# FMU_IO_ports.net
KiCad netlist of a schematic drawn in Altium Designer
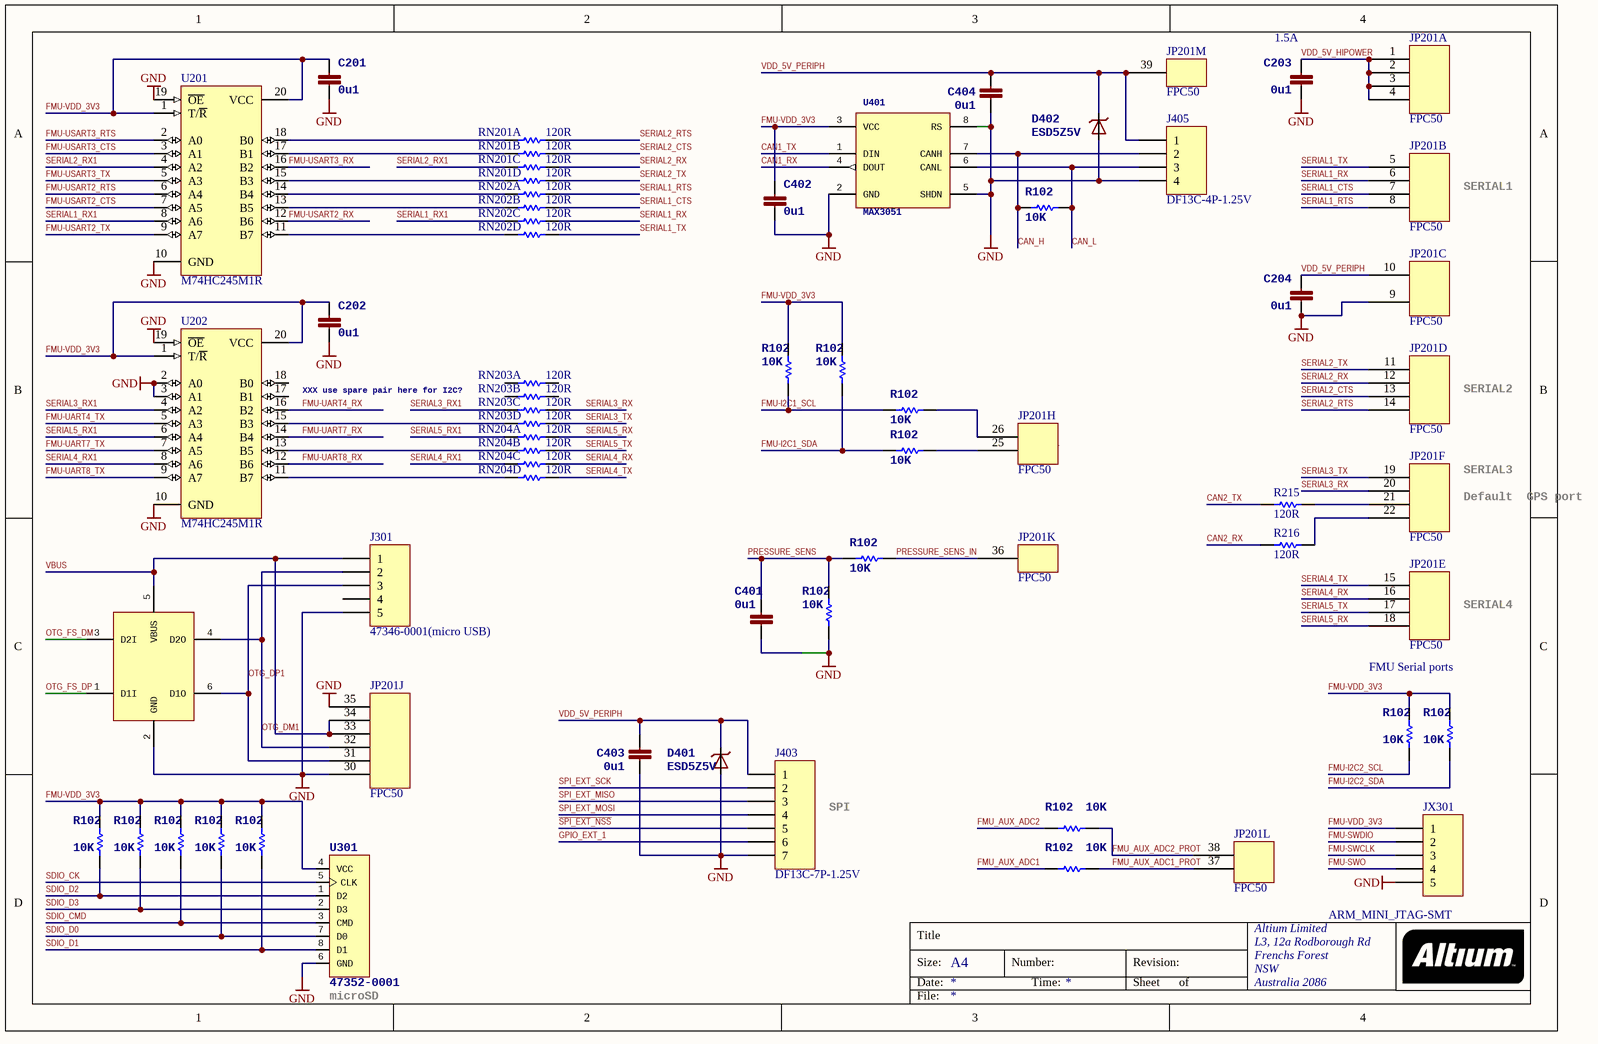
[diagram p0: FMU IO ports.SchDoc]

(export (version "E")
  (design (tool "Eeschema 10.0.6"))
  (components
    (comp (ref "C201")
      (value "0u1")
      (footprint "0603-CAP")
      (description "<b>Capacitor</b>\nStandard 0603 ceramic capacitor, and 0.1\" leaded capacitor.")
      (fields
        (field (name "PARTNO") "CC0402ZRY5V7BB104")
        (field (name ">NAME") "C201")
        (field (name ">VALUE") "0u1")
      )
      (libsource (lib "pixhawk2") (part "CAP0402"))
    )
    (comp (ref "C202")
      (value "0u1")
      (footprint "0603-CAP")
      (description "<b>Capacitor</b>\nStandard 0603 ceramic capacitor, and 0.1\" leaded capacitor.")
      (fields
        (field (name "PARTNO") "CC0402ZRY5V7BB104")
        (field (name ">NAME") "C202")
        (field (name ">VALUE") "0u1")
      )
      (libsource (lib "pixhawk2") (part "CAP0402"))
    )
    (comp (ref "C203")
      (value "0u1")
      (footprint "0603-CAP")
      (description "<b>Capacitor</b>\nStandard 0603 ceramic capacitor, and 0.1\" leaded capacitor.")
      (fields
        (field (name "PARTNO") "CC0805ZKY5V6BB106")
        (field (name ">NAME") "C203")
        (field (name ">VALUE") "0u1")
      )
      (libsource (lib "pixhawk2") (part "CAP0805"))
    )
    (comp (ref "C204")
      (value "0u1")
      (footprint "0603-CAP")
      (description "<b>Capacitor</b>\nStandard 0603 ceramic capacitor, and 0.1\" leaded capacitor.")
      (fields
        (field (name "PARTNO") "CC0805ZKY5V6BB106")
        (field (name ">NAME") "C204")
        (field (name ">VALUE") "0u1")
      )
      (libsource (lib "pixhawk2") (part "CAP0805"))
    )
    (comp (ref "C401")
      (value "0u1")
      (footprint "0603-CAP")
      (description "<b>Capacitor</b>\nStandard 0603 ceramic capacitor, and 0.1\" leaded capacitor.")
      (fields
        (field (name "PARTNO") "CC0402ZRY5V7BB104")
        (field (name ">NAME") "C401")
        (field (name ">VALUE") "0u1")
      )
      (libsource (lib "pixhawk2") (part "CAP0402"))
    )
    (comp (ref "C402")
      (value "0u1")
      (footprint "0603-CAP")
      (description "<b>Capacitor</b>\nStandard 0603 ceramic capacitor, and 0.1\" leaded capacitor.")
      (fields
        (field (name "PARTNO") "CC0402ZRY5V7BB104")
        (field (name ">NAME") "C402")
        (field (name ">VALUE") "0u1")
      )
      (libsource (lib "pixhawk2") (part "CAP0402"))
    )
    (comp (ref "C403")
      (value "0u1")
      (footprint "0603-CAP")
      (description "<b>Capacitor</b>\nStandard 0603 ceramic capacitor, and 0.1\" leaded capacitor.")
      (fields
        (field (name "PARTNO") "CC0805ZKY5V6BB106")
        (field (name ">NAME") "C403")
        (field (name ">VALUE") "0u1")
      )
      (libsource (lib "pixhawk2") (part "CAP0805"))
    )
    (comp (ref "C404")
      (value "0u1")
      (footprint "0603-CAP")
      (description "<b>Capacitor</b>\nStandard 0603 ceramic capacitor, and 0.1\" leaded capacitor.")
      (fields
        (field (name "PARTNO") "CC0805ZKY5V6BB106")
        (field (name ">NAME") "C404")
        (field (name ">VALUE") "0u1")
      )
      (libsource (lib "pixhawk2") (part "CAP0805"))
    )
    (comp (ref "D401") (value "ESD5Z5V") (footprint "SOD523") (libsource (lib "pixhawk2") (part "DIODE-TVS")))
    (comp (ref "D402") (value "ESD5Z5V") (footprint "SOD523") (libsource (lib "pixhawk2") (part "DIODE-TVS")))
    (comp (ref "J301")
      (value "47346-0001(micro USB)")
      (footprint "HDR1X5")
      (description "Header, 5-Pin")
      (fields (field (name "PUBLISHER") "Altium Limited"))
      (libsource (lib "Miscellaneous Connectors") (part "Header 5"))
    )
    (comp (ref "J403")
      (value "DF13C-7P-1.25V")
      (footprint "HDR1X7")
      (description "Header, 7-Pin")
      (fields (field (name "PUBLISHER") "Altium Limited"))
      (libsource (lib "Miscellaneous Connectors") (part "Header 7"))
    )
    (comp (ref "J405")
      (value "DF13C-4P-1.25V")
      (footprint "HDR1X4")
      (description "Header, 4-Pin")
      (fields (field (name "PUBLISHER") "Altium Limited"))
      (libsource (lib "Miscellaneous Connectors") (part "Header 4"))
    )
    (comp (ref "JP201") (value "FPC50") (footprint "FPC-0.5-50下接带锁") (libsource (lib "") (part "FPC50_1")))
    (comp (ref "JX301")
      (value "ARM_MINI_JTAG-SMT")
      (footprint "HDR1X5")
      (description "Header, 5-Pin")
      (fields (field (name "PUBLISHER") "Altium Limited"))
      (libsource (lib "Miscellaneous Connectors") (part "Header 5"))
    )
    (comp (ref "R215")
      (value "120R")
      (footprint "AXIAL-0.5")
      (description "Semiconductor Resistor")
      (fields (field (name "Comment") "Res Semi") (field (name "PUBLISHER") "Altium Limited"))
      (libsource (lib "Miscellaneous Devices") (part "Res Semi"))
    )
    (comp (ref "R216")
      (value "120R")
      (footprint "AXIAL-0.5")
      (description "Semiconductor Resistor")
      (fields (field (name "Comment") "Res Semi") (field (name "PUBLISHER") "Altium Limited"))
      (libsource (lib "Miscellaneous Devices") (part "Res Semi"))
    )
    (comp (ref "R301")
      (value "10K")
      (footprint "0603-RES")
      (fields
        (field (name "PARTNO") "RC0402FR-0710KL")
        (field (name ">NAME") "R102")
        (field (name ">VALUE") "10K")
      )
      (libsource (lib "PX4") (part "RESISTOR0402-RES"))
    )
    (comp (ref "R302")
      (value "10K")
      (footprint "0603-RES")
      (fields
        (field (name "PARTNO") "RC0402FR-0710KL")
        (field (name ">NAME") "R102")
        (field (name ">VALUE") "10K")
      )
      (libsource (lib "PX4") (part "RESISTOR0402-RES"))
    )
    (comp (ref "R303")
      (value "10K")
      (footprint "0603-RES")
      (fields
        (field (name "PARTNO") "RC0402FR-0710KL")
        (field (name ">NAME") "R102")
        (field (name ">VALUE") "10K")
      )
      (libsource (lib "PX4") (part "RESISTOR0402-RES"))
    )
    (comp (ref "R304")
      (value "10K")
      (footprint "0603-RES")
      (fields
        (field (name "PARTNO") "RC0402FR-0710KL")
        (field (name ">NAME") "R102")
        (field (name ">VALUE") "10K")
      )
      (libsource (lib "PX4") (part "RESISTOR0402-RES"))
    )
    (comp (ref "R305")
      (value "10K")
      (footprint "0603-RES")
      (fields
        (field (name "PARTNO") "RC0402FR-0710KL")
        (field (name ">NAME") "R102")
        (field (name ">VALUE") "10K")
      )
      (libsource (lib "PX4") (part "RESISTOR0402-RES"))
    )
    (comp (ref "R306")
      (value "10K")
      (footprint "0603-RES")
      (fields
        (field (name "PARTNO") "RC0402FR-0710KL")
        (field (name ">NAME") "R102")
        (field (name ">VALUE") "10K")
      )
      (libsource (lib "PX4") (part "RESISTOR0402-RES"))
    )
    (comp (ref "R307")
      (value "10K")
      (footprint "0603-RES")
      (fields
        (field (name "PARTNO") "RC0402FR-0710KL")
        (field (name ">NAME") "R102")
        (field (name ">VALUE") "10K")
      )
      (libsource (lib "PX4") (part "RESISTOR0402-RES"))
    )
    (comp (ref "R401")
      (value "10K")
      (footprint "0603-RES")
      (fields
        (field (name "PARTNO") "RC0402FR-0710KL")
        (field (name ">NAME") "R102")
        (field (name ">VALUE") "10K")
      )
      (libsource (lib "PX4") (part "RESISTOR0402-RES"))
    )
    (comp (ref "R402")
      (value "10K")
      (footprint "0603-RES")
      (fields
        (field (name "PARTNO") "RC0402FR-0710KL")
        (field (name ">NAME") "R102")
        (field (name ">VALUE") "10K")
      )
      (libsource (lib "PX4") (part "RESISTOR0402-RES"))
    )
    (comp (ref "R403")
      (value "10K")
      (footprint "0603-RES")
      (fields
        (field (name "PARTNO") "RC0402FR-0710KL")
        (field (name ">NAME") "R102")
        (field (name ">VALUE") "10K")
      )
      (libsource (lib "PX4") (part "RESISTOR0402-RES"))
    )
    (comp (ref "R404")
      (value "10K")
      (footprint "0603-RES")
      (fields
        (field (name "PARTNO") "RC0402FR-0710KL")
        (field (name ">NAME") "R102")
        (field (name ">VALUE") "10K")
      )
      (libsource (lib "PX4") (part "RESISTOR0402-RES"))
    )
    (comp (ref "R405")
      (value "10K")
      (footprint "0603-RES")
      (fields
        (field (name "PARTNO") "RC0402FR-0710KL")
        (field (name ">NAME") "R102")
        (field (name ">VALUE") "10K")
      )
      (libsource (lib "PX4") (part "RESISTOR0402-RES"))
    )
    (comp (ref "R406")
      (value "10K")
      (footprint "0603-RES")
      (fields
        (field (name "PARTNO") "RC0402FR-0710KL")
        (field (name ">NAME") "R102")
        (field (name ">VALUE") "10K")
      )
      (libsource (lib "PX4") (part "RESISTOR0402-RES"))
    )
    (comp (ref "R407")
      (value "10K")
      (footprint "0603-RES")
      (fields
        (field (name "PARTNO") "RC0402FR-0710KL")
        (field (name ">NAME") "R102")
        (field (name ">VALUE") "10K")
      )
      (libsource (lib "PX4") (part "RESISTOR0402-RES"))
    )
    (comp (ref "R408")
      (value "10K")
      (footprint "0603-RES")
      (fields
        (field (name "PARTNO") "RC0402FR-0710KL")
        (field (name ">NAME") "R102")
        (field (name ">VALUE") "10K")
      )
      (libsource (lib "PX4") (part "RESISTOR0402-RES"))
    )
    (comp (ref "R409")
      (value "10K")
      (footprint "0603-RES")
      (fields
        (field (name "PARTNO") "RC0402FR-0710KL")
        (field (name ">NAME") "R102")
        (field (name ">VALUE") "10K")
      )
      (libsource (lib "PX4") (part "RESISTOR0402-RES"))
    )
    (comp (ref "RN201A")
      (value "120R")
      (footprint "AXIAL-0.5")
      (description "Semiconductor Resistor")
      (fields (field (name "Comment") "Res Semi") (field (name "PUBLISHER") "Altium Limited"))
      (libsource (lib "Miscellaneous Devices") (part "Res Semi"))
    )
    (comp (ref "RN201B")
      (value "120R")
      (footprint "AXIAL-0.5")
      (description "Semiconductor Resistor")
      (fields (field (name "Comment") "Res Semi") (field (name "PUBLISHER") "Altium Limited"))
      (libsource (lib "Miscellaneous Devices") (part "Res Semi"))
    )
    (comp (ref "RN201C")
      (value "120R")
      (footprint "AXIAL-0.5")
      (description "Semiconductor Resistor")
      (fields (field (name "Comment") "Res Semi") (field (name "PUBLISHER") "Altium Limited"))
      (libsource (lib "Miscellaneous Devices") (part "Res Semi"))
    )
    (comp (ref "RN201D")
      (value "120R")
      (footprint "AXIAL-0.5")
      (description "Semiconductor Resistor")
      (fields (field (name "Comment") "Res Semi") (field (name "PUBLISHER") "Altium Limited"))
      (libsource (lib "Miscellaneous Devices") (part "Res Semi"))
    )
    (comp (ref "RN202A")
      (value "120R")
      (footprint "AXIAL-0.5")
      (description "Semiconductor Resistor")
      (fields (field (name "Comment") "Res Semi") (field (name "PUBLISHER") "Altium Limited"))
      (libsource (lib "Miscellaneous Devices") (part "Res Semi"))
    )
    (comp (ref "RN202B")
      (value "120R")
      (footprint "AXIAL-0.5")
      (description "Semiconductor Resistor")
      (fields (field (name "Comment") "Res Semi") (field (name "PUBLISHER") "Altium Limited"))
      (libsource (lib "Miscellaneous Devices") (part "Res Semi"))
    )
    (comp (ref "RN202C")
      (value "120R")
      (footprint "AXIAL-0.5")
      (description "Semiconductor Resistor")
      (fields (field (name "Comment") "Res Semi") (field (name "PUBLISHER") "Altium Limited"))
      (libsource (lib "Miscellaneous Devices") (part "Res Semi"))
    )
    (comp (ref "RN202D")
      (value "120R")
      (footprint "AXIAL-0.5")
      (description "Semiconductor Resistor")
      (fields (field (name "Comment") "Res Semi") (field (name "PUBLISHER") "Altium Limited"))
      (libsource (lib "Miscellaneous Devices") (part "Res Semi"))
    )
    (comp (ref "RN203A")
      (value "120R")
      (footprint "AXIAL-0.5")
      (description "Semiconductor Resistor")
      (fields (field (name "Comment") "Res Semi") (field (name "PUBLISHER") "Altium Limited"))
      (libsource (lib "Miscellaneous Devices") (part "Res Semi"))
    )
    (comp (ref "RN203B")
      (value "120R")
      (footprint "AXIAL-0.5")
      (description "Semiconductor Resistor")
      (fields (field (name "Comment") "Res Semi") (field (name "PUBLISHER") "Altium Limited"))
      (libsource (lib "Miscellaneous Devices") (part "Res Semi"))
    )
    (comp (ref "RN203C")
      (value "120R")
      (footprint "AXIAL-0.5")
      (description "Semiconductor Resistor")
      (fields (field (name "Comment") "Res Semi") (field (name "PUBLISHER") "Altium Limited"))
      (libsource (lib "Miscellaneous Devices") (part "Res Semi"))
    )
    (comp (ref "RN203D")
      (value "120R")
      (footprint "AXIAL-0.5")
      (description "Semiconductor Resistor")
      (fields (field (name "Comment") "Res Semi") (field (name "PUBLISHER") "Altium Limited"))
      (libsource (lib "Miscellaneous Devices") (part "Res Semi"))
    )
    (comp (ref "RN204A")
      (value "120R")
      (footprint "AXIAL-0.5")
      (description "Semiconductor Resistor")
      (fields (field (name "Comment") "Res Semi") (field (name "PUBLISHER") "Altium Limited"))
      (libsource (lib "Miscellaneous Devices") (part "Res Semi"))
    )
    (comp (ref "RN204B")
      (value "120R")
      (footprint "AXIAL-0.5")
      (description "Semiconductor Resistor")
      (fields (field (name "Comment") "Res Semi") (field (name "PUBLISHER") "Altium Limited"))
      (libsource (lib "Miscellaneous Devices") (part "Res Semi"))
    )
    (comp (ref "RN204C")
      (value "120R")
      (footprint "AXIAL-0.5")
      (description "Semiconductor Resistor")
      (fields (field (name "Comment") "Res Semi") (field (name "PUBLISHER") "Altium Limited"))
      (libsource (lib "Miscellaneous Devices") (part "Res Semi"))
    )
    (comp (ref "RN204D")
      (value "120R")
      (footprint "AXIAL-0.5")
      (description "Semiconductor Resistor")
      (fields (field (name "Comment") "Res Semi") (field (name "PUBLISHER") "Altium Limited"))
      (libsource (lib "Miscellaneous Devices") (part "Res Semi"))
    )
    (comp (ref "U201")
      (value "M74HC245M1R")
      (footprint "TSSOP20")
      (description "Octal Bus Transceiver 3-State Non-Inverting")
      (fields (field (name "PUBLISHER") "Altium Limited"))
      (libsource (lib "ST Interface Line Transceiver") (part "M74HC245M1R"))
    )
    (comp (ref "U202")
      (value "M74HC245M1R")
      (footprint "TSSOP20")
      (description "Octal Bus Transceiver 3-State Non-Inverting")
      (fields (field (name "PUBLISHER") "Altium Limited"))
      (libsource (lib "ST Interface Line Transceiver") (part "M74HC245M1R"))
    )
    (comp (ref "U301")
      (value "2908-05WB-MG")
      (footprint "MICROSD")
      (fields (field (name ">NAME") "U301") (field (name ">VALUE") "47352-0001"))
      (libsource (lib "PX4") (part "MICROSDSDI"))
    )
    (comp (ref "U302")
      (value "NUF2042XV6")
      (footprint "SOT23-6")
      (fields (field (name "PARTNO") "NUF2042XV6T1G"))
      (libsource (lib "PX4") (part "NUF2042XV6"))
    )
    (comp (ref "U401")
      (value "MAX3051")
      (footprint "SOT23-8")
      (description "3.3-V CAN TRANSCEIVER")
      (fields
        (field (name "PARTNO") "MAX3051EKA")
        (field (name ">NAME") "U401")
        (field (name ">VALUE") "MAX3051")
      )
      (libsource (lib "PX4") (part "MAX3051MAX3051EKA"))
    )
  )
  (nets
    (net (code "1") (name "/CAN1_RX") (class "Default")
      (node (ref "U401") (pin "4") (pinfunction "DOUT_4") (pintype "output"))
    )
    (net (code "2") (name "/CAN1_TX") (class "Default")
      (node (ref "U401") (pin "1") (pinfunction "DIN_1") (pintype "passive"))
    )
    (net (code "3") (name "/CAN2_RX") (class "Default")
      (node (ref "R216") (pin "1") (pinfunction "1_1") (pintype "passive"))
    )
    (net (code "4") (name "/CAN2_TX") (class "Default")
      (node (ref "R215") (pin "1") (pinfunction "1_1") (pintype "passive"))
    )
    (net (code "5") (name "/CAN_H") (class "Default")
      (node (ref "J405") (pin "2") (pinfunction "2_2") (pintype "passive"))
      (node (ref "R409") (pin "P$1") (pinfunction "1_P$1") (pintype "passive"))
      (node (ref "U401") (pin "7") (pinfunction "CANH_7") (pintype "passive"))
    )
    (net (code "6") (name "/CAN_L") (class "Default")
      (node (ref "J405") (pin "3") (pinfunction "3_3") (pintype "passive"))
      (node (ref "R409") (pin "P$2") (pinfunction "2_P$2") (pintype "passive"))
      (node (ref "U401") (pin "6") (pinfunction "CANL_6") (pintype "passive"))
    )
    (net (code "7") (name "/FMU-I2C1_SCL") (class "Default")
      (node (ref "R401") (pin "P$1") (pinfunction "1_P$1") (pintype "passive"))
      (node (ref "R404") (pin "P$1") (pinfunction "1_P$1") (pintype "passive"))
    )
    (net (code "8") (name "/FMU-I2C1_SDA") (class "Default")
      (node (ref "R402") (pin "P$1") (pinfunction "1_P$1") (pintype "passive"))
      (node (ref "R405") (pin "P$1") (pinfunction "1_P$1") (pintype "passive"))
    )
    (net (code "9") (name "/FMU-I2C2_SCL") (class "Default")
      (node (ref "R306") (pin "P$1") (pinfunction "1_P$1") (pintype "passive"))
    )
    (net (code "10") (name "/FMU-I2C2_SDA") (class "Default")
      (node (ref "R307") (pin "P$1") (pinfunction "1_P$1") (pintype "passive"))
    )
    (net (code "11") (name "/FMU-SWCLK") (class "Default")
      (node (ref "JX301") (pin "3") (pinfunction "3_3") (pintype "passive"))
    )
    (net (code "12") (name "/FMU-SWDIO") (class "Default")
      (node (ref "JX301") (pin "2") (pinfunction "2_2") (pintype "passive"))
    )
    (net (code "13") (name "/FMU-SWO") (class "Default")
      (node (ref "JX301") (pin "4") (pinfunction "4_4") (pintype "passive"))
    )
    (net (code "14") (name "/FMU-UART4_RX") (class "Default")
      (node (ref "U202") (pin "16") (pinfunction "B2_16") (pintype "bidirectional"))
    )
    (net (code "15") (name "/FMU-UART4_TX") (class "Default")
      (node (ref "U202") (pin "5") (pinfunction "A3_5") (pintype "bidirectional"))
    )
    (net (code "16") (name "/FMU-UART7_RX") (class "Default")
      (node (ref "U202") (pin "14") (pinfunction "B4_14") (pintype "bidirectional"))
    )
    (net (code "17") (name "/FMU-UART7_TX") (class "Default")
      (node (ref "U202") (pin "7") (pinfunction "A5_7") (pintype "bidirectional"))
    )
    (net (code "18") (name "/FMU-UART8_RX") (class "Default")
      (node (ref "U202") (pin "12") (pinfunction "B6_12") (pintype "bidirectional"))
    )
    (net (code "19") (name "/FMU-UART8_TX") (class "Default")
      (node (ref "U202") (pin "9") (pinfunction "A7_9") (pintype "bidirectional"))
    )
    (net (code "20") (name "/FMU-USART2_CTS") (class "Default")
      (node (ref "U201") (pin "7") (pinfunction "A5_7") (pintype "bidirectional"))
    )
    (net (code "21") (name "/FMU-USART2_RTS") (class "Default")
      (node (ref "U201") (pin "6") (pinfunction "A4_6") (pintype "bidirectional"))
    )
    (net (code "22") (name "/FMU-USART2_RX") (class "Default")
      (node (ref "U201") (pin "12") (pinfunction "B6_12") (pintype "bidirectional"))
    )
    (net (code "23") (name "/FMU-USART2_TX") (class "Default")
      (node (ref "U201") (pin "9") (pinfunction "A7_9") (pintype "bidirectional"))
    )
    (net (code "24") (name "/FMU-USART3_CTS") (class "Default")
      (node (ref "U201") (pin "3") (pinfunction "A1_3") (pintype "bidirectional"))
    )
    (net (code "25") (name "/FMU-USART3_RTS") (class "Default")
      (node (ref "U201") (pin "2") (pinfunction "A0_2") (pintype "bidirectional"))
    )
    (net (code "26") (name "/FMU-USART3_RX") (class "Default")
      (node (ref "U201") (pin "16") (pinfunction "B2_16") (pintype "bidirectional"))
    )
    (net (code "27") (name "/FMU-USART3_TX") (class "Default")
      (node (ref "U201") (pin "5") (pinfunction "A3_5") (pintype "bidirectional"))
    )
    (net (code "28") (name "/FMU-VDD_3V3") (class "Default")
      (node (ref "C201") (pin "P$1") (pinfunction "1_P$1") (pintype "passive"))
      (node (ref "C202") (pin "P$1") (pinfunction "1_P$1") (pintype "passive"))
      (node (ref "C402") (pin "P$1") (pinfunction "1_P$1") (pintype "passive"))
      (node (ref "JX301") (pin "1") (pinfunction "1_1") (pintype "passive"))
      (node (ref "R301") (pin "P$2") (pinfunction "2_P$2") (pintype "passive"))
      (node (ref "R302") (pin "P$2") (pinfunction "2_P$2") (pintype "passive"))
      (node (ref "R303") (pin "P$2") (pinfunction "2_P$2") (pintype "passive"))
      (node (ref "R304") (pin "P$2") (pinfunction "2_P$2") (pintype "passive"))
      (node (ref "R305") (pin "P$2") (pinfunction "2_P$2") (pintype "passive"))
      (node (ref "R306") (pin "P$2") (pinfunction "2_P$2") (pintype "passive"))
      (node (ref "R307") (pin "P$2") (pinfunction "2_P$2") (pintype "passive"))
      (node (ref "R401") (pin "P$2") (pinfunction "2_P$2") (pintype "passive"))
      (node (ref "R402") (pin "P$2") (pinfunction "2_P$2") (pintype "passive"))
      (node (ref "U201") (pin "1") (pinfunction "T/~{R}_1") (pintype "input"))
      (node (ref "U201") (pin "20") (pinfunction "VCC_20") (pintype "power_in"))
      (node (ref "U202") (pin "1") (pinfunction "T/~{R}_1") (pintype "input"))
      (node (ref "U202") (pin "20") (pinfunction "VCC_20") (pintype "power_in"))
      (node (ref "U301") (pin "4") (pinfunction "VCC_4") (pintype "passive"))
      (node (ref "U401") (pin "3") (pinfunction "VCC_3") (pintype "passive"))
    )
    (net (code "29") (name "/FMU_AUX_ADC1") (class "Default")
      (node (ref "R408") (pin "P$1") (pinfunction "1_P$1") (pintype "passive"))
    )
    (net (code "30") (name "/FMU_AUX_ADC1_PROT") (class "Default")
      (node (ref "JP201") (pin "37") (pintype "passive"))
      (node (ref "R408") (pin "P$2") (pinfunction "2_P$2") (pintype "passive"))
    )
    (net (code "31") (name "/FMU_AUX_ADC2") (class "Default")
      (node (ref "R407") (pin "P$1") (pinfunction "1_P$1") (pintype "passive"))
    )
    (net (code "32") (name "/FMU_AUX_ADC2_PROT") (class "Default")
      (node (ref "JP201") (pin "38") (pintype "passive"))
      (node (ref "R407") (pin "P$2") (pinfunction "2_P$2") (pintype "passive"))
    )
    (net (code "33") (name "/GPIO_EXT_1") (class "Default")
      (node (ref "J403") (pin "6") (pinfunction "6_6") (pintype "passive"))
    )
    (net (code "34") (name "/OTG_DM1") (class "Default")
      (node (ref "J301") (pin "2") (pinfunction "2_2") (pintype "passive"))
      (node (ref "JP201") (pin "32") (pintype "passive"))
      (node (ref "U302") (pin "4") (pinfunction "D2O_4") (pintype "passive"))
    )
    (net (code "35") (name "/OTG_DP1") (class "Default")
      (node (ref "J301") (pin "3") (pinfunction "3_3") (pintype "passive"))
      (node (ref "JP201") (pin "31") (pintype "passive"))
      (node (ref "U302") (pin "6") (pinfunction "D1O_6") (pintype "passive"))
    )
    (net (code "36") (name "/OTG_FS_DM") (class "Default")
      (node (ref "U302") (pin "3") (pinfunction "D2I_3") (pintype "passive"))
    )
    (net (code "37") (name "/OTG_FS_DP") (class "Default")
      (node (ref "U302") (pin "1") (pinfunction "D1I_1") (pintype "passive"))
    )
    (net (code "38") (name "/PRESSURE_SENS") (class "Default")
      (node (ref "C401") (pin "P$1") (pinfunction "1_P$1") (pintype "passive"))
      (node (ref "R403") (pin "P$2") (pinfunction "2_P$2") (pintype "passive"))
      (node (ref "R406") (pin "P$1") (pinfunction "1_P$1") (pintype "passive"))
    )
    (net (code "39") (name "/PRESSURE_SENS_IN") (class "Default")
      (node (ref "JP201") (pin "36") (pintype "passive"))
      (node (ref "R406") (pin "P$2") (pinfunction "2_P$2") (pintype "passive"))
    )
    (net (code "40") (name "/SDIO_CK") (class "Default")
      (node (ref "U301") (pin "5") (pinfunction "CLK_5") (pintype "passive"))
    )
    (net (code "41") (name "/SDIO_CMD") (class "Default")
      (node (ref "R303") (pin "P$1") (pinfunction "1_P$1") (pintype "passive"))
      (node (ref "U301") (pin "3") (pinfunction "CMD_3") (pintype "passive"))
    )
    (net (code "42") (name "/SDIO_D0") (class "Default")
      (node (ref "R304") (pin "P$1") (pinfunction "1_P$1") (pintype "passive"))
      (node (ref "U301") (pin "7") (pinfunction "D0_7") (pintype "passive"))
    )
    (net (code "43") (name "/SDIO_D1") (class "Default")
      (node (ref "R305") (pin "P$1") (pinfunction "1_P$1") (pintype "passive"))
      (node (ref "U301") (pin "8") (pinfunction "D1_8") (pintype "passive"))
    )
    (net (code "44") (name "/SDIO_D2") (class "Default")
      (node (ref "R301") (pin "P$1") (pinfunction "1_P$1") (pintype "passive"))
      (node (ref "U301") (pin "1") (pinfunction "D2_1") (pintype "passive"))
    )
    (net (code "45") (name "/SDIO_D3") (class "Default")
      (node (ref "R302") (pin "P$1") (pinfunction "1_P$1") (pintype "passive"))
      (node (ref "U301") (pin "2") (pinfunction "D3_2") (pintype "passive"))
    )
    (net (code "46") (name "/SERIAL1_CTS") (class "Default")
      (node (ref "JP201") (pin "7") (pintype "passive"))
      (node (ref "RN202B") (pin "1") (pinfunction "1_1") (pintype "passive"))
    )
    (net (code "47") (name "/SERIAL1_RTS") (class "Default")
      (node (ref "JP201") (pin "8") (pintype "passive"))
      (node (ref "RN202A") (pin "1") (pinfunction "1_1") (pintype "passive"))
    )
    (net (code "48") (name "/SERIAL1_RX") (class "Default")
      (node (ref "JP201") (pin "6") (pintype "passive"))
      (node (ref "RN202C") (pin "1") (pinfunction "1_1") (pintype "passive"))
    )
    (net (code "49") (name "/SERIAL1_RX1") (class "Default")
      (node (ref "RN202C") (pin "2") (pinfunction "2_2") (pintype "passive"))
      (node (ref "U201") (pin "8") (pinfunction "A6_8") (pintype "bidirectional"))
    )
    (net (code "50") (name "/SERIAL1_TX") (class "Default")
      (node (ref "JP201") (pin "5") (pintype "passive"))
      (node (ref "RN202D") (pin "1") (pinfunction "1_1") (pintype "passive"))
    )
    (net (code "51") (name "/SERIAL2_CTS") (class "Default")
      (node (ref "JP201") (pin "13") (pintype "passive"))
      (node (ref "RN201B") (pin "1") (pinfunction "1_1") (pintype "passive"))
    )
    (net (code "52") (name "/SERIAL2_RTS") (class "Default")
      (node (ref "JP201") (pin "14") (pintype "passive"))
      (node (ref "RN201A") (pin "1") (pinfunction "1_1") (pintype "passive"))
    )
    (net (code "53") (name "/SERIAL2_RX") (class "Default")
      (node (ref "JP201") (pin "12") (pintype "passive"))
      (node (ref "RN201C") (pin "1") (pinfunction "1_1") (pintype "passive"))
    )
    (net (code "54") (name "/SERIAL2_RX1") (class "Default")
      (node (ref "RN201C") (pin "2") (pinfunction "2_2") (pintype "passive"))
      (node (ref "U201") (pin "4") (pinfunction "A2_4") (pintype "bidirectional"))
    )
    (net (code "55") (name "/SERIAL2_TX") (class "Default")
      (node (ref "JP201") (pin "11") (pintype "passive"))
      (node (ref "RN201D") (pin "1") (pinfunction "1_1") (pintype "passive"))
    )
    (net (code "56") (name "/SERIAL3_RX") (class "Default")
      (node (ref "JP201") (pin "20") (pintype "passive"))
      (node (ref "RN203C") (pin "1") (pinfunction "1_1") (pintype "passive"))
    )
    (net (code "57") (name "/SERIAL3_RX1") (class "Default")
      (node (ref "RN203C") (pin "2") (pinfunction "2_2") (pintype "passive"))
      (node (ref "U202") (pin "4") (pinfunction "A2_4") (pintype "bidirectional"))
    )
    (net (code "58") (name "/SERIAL3_TX") (class "Default")
      (node (ref "JP201") (pin "19") (pintype "passive"))
      (node (ref "RN203D") (pin "1") (pinfunction "1_1") (pintype "passive"))
    )
    (net (code "59") (name "/SERIAL4_RX") (class "Default")
      (node (ref "JP201") (pin "16") (pintype "passive"))
      (node (ref "RN204C") (pin "1") (pinfunction "1_1") (pintype "passive"))
    )
    (net (code "60") (name "/SERIAL4_RX1") (class "Default")
      (node (ref "RN204C") (pin "2") (pinfunction "2_2") (pintype "passive"))
      (node (ref "U202") (pin "8") (pinfunction "A6_8") (pintype "bidirectional"))
    )
    (net (code "61") (name "/SERIAL4_TX") (class "Default")
      (node (ref "JP201") (pin "15") (pintype "passive"))
      (node (ref "RN204D") (pin "1") (pinfunction "1_1") (pintype "passive"))
    )
    (net (code "62") (name "/SERIAL5_RX") (class "Default")
      (node (ref "JP201") (pin "18") (pintype "passive"))
      (node (ref "RN204A") (pin "1") (pinfunction "1_1") (pintype "passive"))
    )
    (net (code "63") (name "/SERIAL5_RX1") (class "Default")
      (node (ref "RN204A") (pin "2") (pinfunction "2_2") (pintype "passive"))
      (node (ref "U202") (pin "6") (pinfunction "A4_6") (pintype "bidirectional"))
    )
    (net (code "64") (name "/SERIAL5_TX") (class "Default")
      (node (ref "JP201") (pin "17") (pintype "passive"))
      (node (ref "RN204B") (pin "1") (pinfunction "1_1") (pintype "passive"))
    )
    (net (code "65") (name "/SPI_EXT_MISO") (class "Default")
      (node (ref "J403") (pin "3") (pinfunction "3_3") (pintype "passive"))
    )
    (net (code "66") (name "/SPI_EXT_MOSI") (class "Default")
      (node (ref "J403") (pin "4") (pinfunction "4_4") (pintype "passive"))
    )
    (net (code "67") (name "/SPI_EXT_SCK") (class "Default")
      (node (ref "J403") (pin "2") (pinfunction "2_2") (pintype "passive"))
    )
    (net (code "68") (name "/VBUS") (class "Default")
      (node (ref "J301") (pin "1") (pinfunction "1_1") (pintype "passive"))
      (node (ref "JP201") (pin "33") (pintype "passive"))
      (node (ref "JP201") (pin "34") (pintype "passive"))
      (node (ref "U302") (pin "5") (pinfunction "VBUS_5") (pintype "passive"))
    )
    (net (code "69") (name "/VDD_5V_HIPOWER") (class "Default")
      (node (ref "C203") (pin "P$1") (pinfunction "1_P$1") (pintype "passive"))
      (node (ref "JP201") (pin "1") (pintype "passive"))
      (node (ref "JP201") (pin "2") (pintype "passive"))
      (node (ref "JP201") (pin "3") (pintype "passive"))
      (node (ref "JP201") (pin "4") (pintype "passive"))
    )
    (net (code "70") (name "/VDD_5V_PERIPH") (class "Default")
      (node (ref "C204") (pin "P$1") (pinfunction "1_P$1") (pintype "passive"))
      (node (ref "C403") (pin "P$1") (pinfunction "1_P$1") (pintype "passive"))
      (node (ref "C404") (pin "P$1") (pinfunction "1_P$1") (pintype "passive"))
      (node (ref "D401") (pin "C") (pinfunction "C_C") (pintype "passive"))
      (node (ref "D402") (pin "C") (pinfunction "C_C") (pintype "passive"))
      (node (ref "J403") (pin "1") (pinfunction "1_1") (pintype "passive"))
      (node (ref "J405") (pin "1") (pinfunction "1_1") (pintype "passive"))
      (node (ref "JP201") (pin "10") (pintype "passive"))
      (node (ref "JP201") (pin "39") (pintype "passive"))
    )
    (net (code "71") (name "/~{SPI_EXT_NSS}") (class "Default")
      (node (ref "J403") (pin "5") (pinfunction "5_5") (pintype "passive"))
    )
    (net (code "72") (name "GND") (class "Default")
      (node (ref "C201") (pin "P$2") (pinfunction "2_P$2") (pintype "passive"))
      (node (ref "C202") (pin "P$2") (pinfunction "2_P$2") (pintype "passive"))
      (node (ref "C203") (pin "P$2") (pinfunction "2_P$2") (pintype "passive"))
      (node (ref "C204") (pin "P$2") (pinfunction "2_P$2") (pintype "passive"))
      (node (ref "C401") (pin "P$2") (pinfunction "2_P$2") (pintype "passive"))
      (node (ref "C402") (pin "P$2") (pinfunction "2_P$2") (pintype "passive"))
      (node (ref "C403") (pin "P$2") (pinfunction "2_P$2") (pintype "passive"))
      (node (ref "C404") (pin "P$2") (pinfunction "2_P$2") (pintype "passive"))
      (node (ref "D401") (pin "A") (pinfunction "A_A") (pintype "passive"))
      (node (ref "D402") (pin "A") (pinfunction "A_A") (pintype "passive"))
      (node (ref "J301") (pin "5") (pinfunction "5_5") (pintype "passive"))
      (node (ref "J403") (pin "7") (pinfunction "7_7") (pintype "passive"))
      (node (ref "J405") (pin "4") (pinfunction "4_4") (pintype "passive"))
      (node (ref "JP201") (pin "30") (pintype "passive"))
      (node (ref "JP201") (pin "35") (pintype "passive"))
      (node (ref "JP201") (pin "9") (pintype "passive"))
      (node (ref "JX301") (pin "5") (pinfunction "5_5") (pintype "passive"))
      (node (ref "R403") (pin "P$1") (pinfunction "1_P$1") (pintype "passive"))
      (node (ref "U201") (pin "10") (pinfunction "GND_10") (pintype "power_in"))
      (node (ref "U201") (pin "19") (pinfunction "~{OE}_19") (pintype "input"))
      (node (ref "U202") (pin "10") (pinfunction "GND_10") (pintype "power_in"))
      (node (ref "U202") (pin "19") (pinfunction "~{OE}_19") (pintype "input"))
      (node (ref "U202") (pin "2") (pinfunction "A0_2") (pintype "bidirectional"))
      (node (ref "U202") (pin "3") (pinfunction "A1_3") (pintype "bidirectional"))
      (node (ref "U301") (pin "6") (pinfunction "GND_6") (pintype "open_emitter"))
      (node (ref "U302") (pin "2") (pinfunction "GND_2") (pintype "passive"))
      (node (ref "U401") (pin "2") (pinfunction "GND_2") (pintype "open_emitter"))
      (node (ref "U401") (pin "5") (pinfunction "SHDN_5") (pintype "passive"))
      (node (ref "U401") (pin "8") (pinfunction "RS_8") (pintype "passive"))
    )
    (net (code "73") (name "Net-(JP201-Pad21)") (class "Default")
      (node (ref "JP201") (pin "21") (pintype "passive"))
      (node (ref "R215") (pin "2") (pinfunction "2_2") (pintype "passive"))
    )
    (net (code "74") (name "Net-(JP201-Pad22)") (class "Default")
      (node (ref "JP201") (pin "22") (pintype "passive"))
      (node (ref "R216") (pin "2") (pinfunction "2_2") (pintype "passive"))
    )
    (net (code "75") (name "Net-(R404-2)") (class "Default")
      (node (ref "JP201") (pin "26") (pintype "passive"))
      (node (ref "R404") (pin "P$2") (pinfunction "2_P$2") (pintype "passive"))
    )
    (net (code "76") (name "Net-(R405-2)") (class "Default")
      (node (ref "JP201") (pin "25") (pintype "passive"))
      (node (ref "R405") (pin "P$2") (pinfunction "2_P$2") (pintype "passive"))
    )
    (net (code "77") (name "Net-(U201-B0)") (class "Default")
      (node (ref "RN201A") (pin "2") (pinfunction "2_2") (pintype "passive"))
      (node (ref "U201") (pin "18") (pinfunction "B0_18") (pintype "bidirectional"))
    )
    (net (code "78") (name "Net-(U201-B1)") (class "Default")
      (node (ref "RN201B") (pin "2") (pinfunction "2_2") (pintype "passive"))
      (node (ref "U201") (pin "17") (pinfunction "B1_17") (pintype "bidirectional"))
    )
    (net (code "79") (name "Net-(U201-B3)") (class "Default")
      (node (ref "RN201D") (pin "2") (pinfunction "2_2") (pintype "passive"))
      (node (ref "U201") (pin "15") (pinfunction "B3_15") (pintype "bidirectional"))
    )
    (net (code "80") (name "Net-(U201-B4)") (class "Default")
      (node (ref "RN202A") (pin "2") (pinfunction "2_2") (pintype "passive"))
      (node (ref "U201") (pin "14") (pinfunction "B4_14") (pintype "bidirectional"))
    )
    (net (code "81") (name "Net-(U201-B5)") (class "Default")
      (node (ref "RN202B") (pin "2") (pinfunction "2_2") (pintype "passive"))
      (node (ref "U201") (pin "13") (pinfunction "B5_13") (pintype "bidirectional"))
    )
    (net (code "82") (name "Net-(U201-B7)") (class "Default")
      (node (ref "RN202D") (pin "2") (pinfunction "2_2") (pintype "passive"))
      (node (ref "U201") (pin "11") (pinfunction "B7_11") (pintype "bidirectional"))
    )
    (net (code "83") (name "Net-(U202-B3)") (class "Default")
      (node (ref "RN203D") (pin "2") (pinfunction "2_2") (pintype "passive"))
      (node (ref "U202") (pin "15") (pinfunction "B3_15") (pintype "bidirectional"))
    )
    (net (code "84") (name "Net-(U202-B5)") (class "Default")
      (node (ref "RN204B") (pin "2") (pinfunction "2_2") (pintype "passive"))
      (node (ref "U202") (pin "13") (pinfunction "B5_13") (pintype "bidirectional"))
    )
    (net (code "85") (name "Net-(U202-B7)") (class "Default")
      (node (ref "RN204D") (pin "2") (pinfunction "2_2") (pintype "passive"))
      (node (ref "U202") (pin "11") (pinfunction "B7_11") (pintype "bidirectional"))
    )
    (net (code "86") (name "unconnected-(J301-Pad4)") (class "Default")
      (node (ref "J301") (pin "4") (pinfunction "4_4") (pintype "passive"))
    )
    (net (code "87") (name "unconnected-(RN203A-Pad1)") (class "Default")
      (node (ref "RN203A") (pin "1") (pinfunction "1_1") (pintype "passive"))
    )
    (net (code "88") (name "unconnected-(RN203A-Pad2)") (class "Default")
      (node (ref "RN203A") (pin "2") (pinfunction "2_2") (pintype "passive"))
    )
    (net (code "89") (name "unconnected-(RN203B-Pad1)") (class "Default")
      (node (ref "RN203B") (pin "1") (pinfunction "1_1") (pintype "passive"))
    )
    (net (code "90") (name "unconnected-(RN203B-Pad2)") (class "Default")
      (node (ref "RN203B") (pin "2") (pinfunction "2_2") (pintype "passive"))
    )
    (net (code "91") (name "unconnected-(U202-B0-Pad18)") (class "Default")
      (node (ref "U202") (pin "18") (pinfunction "B0_18") (pintype "bidirectional"))
    )
    (net (code "92") (name "unconnected-(U202-B1-Pad17)") (class "Default")
      (node (ref "U202") (pin "17") (pinfunction "B1_17") (pintype "bidirectional"))
    )
  )
)
